# 1-4.net
KiCad netlist of a schematic drawn in EAGLE
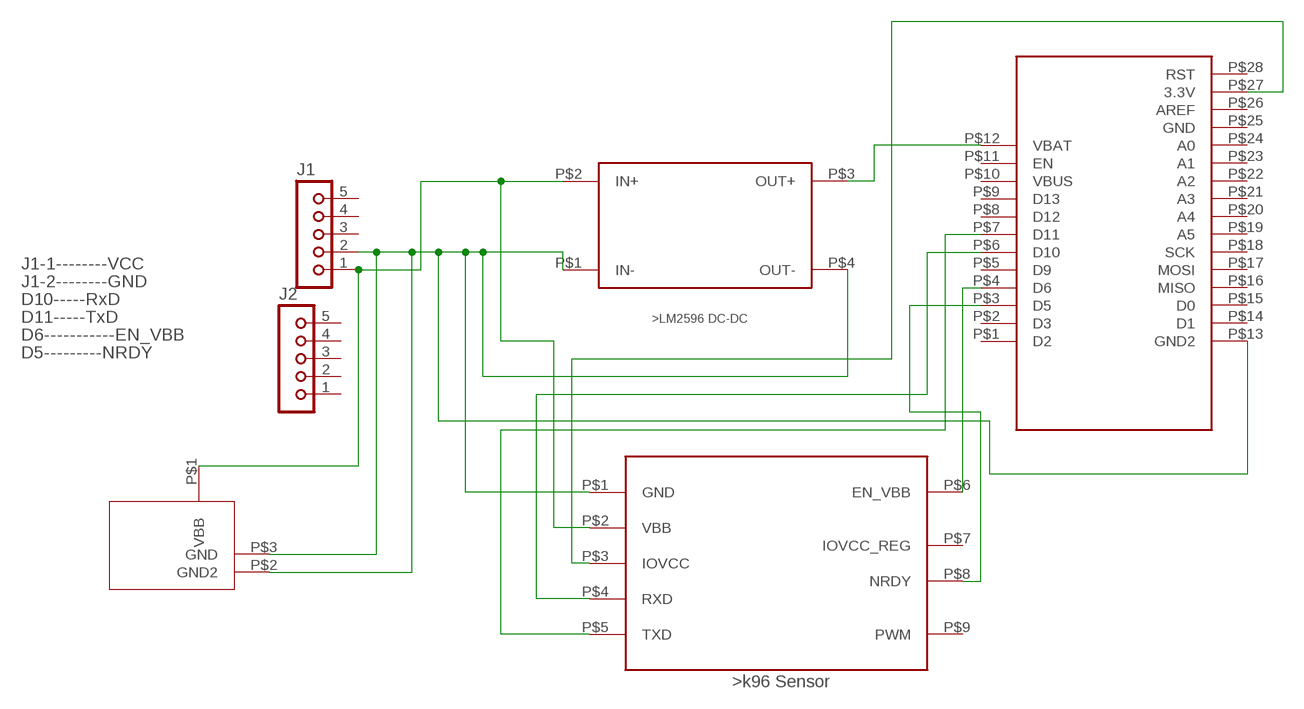
[diagram p0: schematic, sheet 1]

(export (version "E")
  (design (tool "Eeschema 10.0.6"))
  (components
    (comp (ref "DCDC1")
      (value "DCDC")
      (footprint "eagle-import:DCDC")
      (libsource (lib "eagle-import") (part "DCDC"))
    )
    (comp (ref "FEATHER1")
      (value "FEATHER")
      (footprint "eagle-import:FEATHER")
      (libsource (lib "eagle-import") (part "FEATHER"))
    )
    (comp (ref "J1")
      (value "JU05")
      (footprint "eagle-import:JU05")
      (libsource (lib "eagle-import") (part "JU05"))
    )
    (comp (ref "J2")
      (value "JU05")
      (footprint "eagle-import:JU05")
      (libsource (lib "eagle-import") (part "JU05"))
    )
    (comp (ref "K96SENSOR1")
      (value "K96SENSOR")
      (footprint "eagle-import:K96SENSOR")
      (libsource (lib "eagle-import") (part "K96SENSOR"))
    )
    (comp (ref "U$1")
      (value "POWER")
      (footprint "eagle-import:POWERIN")
      (libsource (lib "eagle-import") (part "POWER"))
    )
  )
  (nets
    (net (code "1") (name "Net-(DCDC1-IN+)") (class "Default")
      (node (ref "DCDC1") (pin "P$2") (pinfunction "IN+_P$2") (pintype "bidirectional"))
      (node (ref "J1") (pin "1") (pinfunction "1_1") (pintype "passive"))
      (node (ref "K96SENSOR1") (pin "P$2") (pinfunction "VBB_P$2") (pintype "bidirectional"))
      (node (ref "U$1") (pin "P$1") (pinfunction "VBB_P$1") (pintype "bidirectional"))
    )
    (net (code "2") (name "Net-(DCDC1-IN-)") (class "Default")
      (node (ref "DCDC1") (pin "P$1") (pinfunction "IN-_P$1") (pintype "bidirectional"))
      (node (ref "DCDC1") (pin "P$4") (pinfunction "OUT-_P$4") (pintype "bidirectional"))
      (node (ref "FEATHER1") (pin "P$13") (pinfunction "GND2_P$13") (pintype "bidirectional"))
      (node (ref "J1") (pin "2") (pinfunction "2_2") (pintype "passive"))
      (node (ref "K96SENSOR1") (pin "P$1") (pinfunction "GND_P$1") (pintype "bidirectional"))
      (node (ref "U$1") (pin "P$2") (pinfunction "GND2_P$2") (pintype "bidirectional"))
      (node (ref "U$1") (pin "P$3") (pinfunction "GND_P$3") (pintype "bidirectional"))
    )
    (net (code "3") (name "Net-(DCDC1-OUT+)") (class "Default")
      (node (ref "DCDC1") (pin "P$3") (pinfunction "OUT+_P$3") (pintype "bidirectional"))
      (node (ref "FEATHER1") (pin "P$12") (pinfunction "VBAT_P$12") (pintype "bidirectional"))
    )
    (net (code "4") (name "Net-(FEATHER1-3.3V)") (class "Default")
      (node (ref "FEATHER1") (pin "P$27") (pinfunction "3.3V_P$27") (pintype "bidirectional"))
      (node (ref "K96SENSOR1") (pin "P$3") (pinfunction "IOVCC_P$3") (pintype "bidirectional"))
    )
    (net (code "5") (name "Net-(FEATHER1-D5)") (class "Default")
      (node (ref "FEATHER1") (pin "P$3") (pinfunction "D5_P$3") (pintype "bidirectional"))
      (node (ref "K96SENSOR1") (pin "P$8") (pinfunction "NRDY_P$8") (pintype "bidirectional"))
    )
    (net (code "6") (name "Net-(FEATHER1-D6)") (class "Default")
      (node (ref "FEATHER1") (pin "P$4") (pinfunction "D6_P$4") (pintype "bidirectional"))
      (node (ref "K96SENSOR1") (pin "P$6") (pinfunction "EN_VBB_P$6") (pintype "bidirectional"))
    )
    (net (code "7") (name "Net-(FEATHER1-D10)") (class "Default")
      (node (ref "FEATHER1") (pin "P$6") (pinfunction "D10_P$6") (pintype "bidirectional"))
      (node (ref "K96SENSOR1") (pin "P$4") (pinfunction "RXD_P$4") (pintype "bidirectional"))
    )
    (net (code "8") (name "Net-(FEATHER1-D11)") (class "Default")
      (node (ref "FEATHER1") (pin "P$7") (pinfunction "D11_P$7") (pintype "bidirectional"))
      (node (ref "K96SENSOR1") (pin "P$5") (pinfunction "TXD_P$5") (pintype "bidirectional"))
    )
    (net (code "9") (name "unconnected-(FEATHER1-A0-PadP$24)") (class "Default")
      (node (ref "FEATHER1") (pin "P$24") (pinfunction "A0_P$24") (pintype "bidirectional"))
    )
    (net (code "10") (name "unconnected-(FEATHER1-A1-PadP$23)") (class "Default")
      (node (ref "FEATHER1") (pin "P$23") (pinfunction "A1_P$23") (pintype "bidirectional"))
    )
    (net (code "11") (name "unconnected-(FEATHER1-A2-PadP$22)") (class "Default")
      (node (ref "FEATHER1") (pin "P$22") (pinfunction "A2_P$22") (pintype "bidirectional"))
    )
    (net (code "12") (name "unconnected-(FEATHER1-A3-PadP$21)") (class "Default")
      (node (ref "FEATHER1") (pin "P$21") (pinfunction "A3_P$21") (pintype "bidirectional"))
    )
    (net (code "13") (name "unconnected-(FEATHER1-A4-PadP$20)") (class "Default")
      (node (ref "FEATHER1") (pin "P$20") (pinfunction "A4_P$20") (pintype "bidirectional"))
    )
    (net (code "14") (name "unconnected-(FEATHER1-A5-PadP$19)") (class "Default")
      (node (ref "FEATHER1") (pin "P$19") (pinfunction "A5_P$19") (pintype "bidirectional"))
    )
    (net (code "15") (name "unconnected-(FEATHER1-AREF-PadP$26)") (class "Default")
      (node (ref "FEATHER1") (pin "P$26") (pinfunction "AREF_P$26") (pintype "bidirectional"))
    )
    (net (code "16") (name "unconnected-(FEATHER1-D0-PadP$15)") (class "Default")
      (node (ref "FEATHER1") (pin "P$15") (pinfunction "D0_P$15") (pintype "bidirectional"))
    )
    (net (code "17") (name "unconnected-(FEATHER1-D1-PadP$14)") (class "Default")
      (node (ref "FEATHER1") (pin "P$14") (pinfunction "D1_P$14") (pintype "bidirectional"))
    )
    (net (code "18") (name "unconnected-(FEATHER1-D2-PadP$1)") (class "Default")
      (node (ref "FEATHER1") (pin "P$1") (pinfunction "D2_P$1") (pintype "bidirectional"))
    )
    (net (code "19") (name "unconnected-(FEATHER1-D3-PadP$2)") (class "Default")
      (node (ref "FEATHER1") (pin "P$2") (pinfunction "D3_P$2") (pintype "bidirectional"))
    )
    (net (code "20") (name "unconnected-(FEATHER1-D9-PadP$5)") (class "Default")
      (node (ref "FEATHER1") (pin "P$5") (pinfunction "D9_P$5") (pintype "bidirectional"))
    )
    (net (code "21") (name "unconnected-(FEATHER1-D12-PadP$8)") (class "Default")
      (node (ref "FEATHER1") (pin "P$8") (pinfunction "D12_P$8") (pintype "bidirectional"))
    )
    (net (code "22") (name "unconnected-(FEATHER1-D13-PadP$9)") (class "Default")
      (node (ref "FEATHER1") (pin "P$9") (pinfunction "D13_P$9") (pintype "bidirectional"))
    )
    (net (code "23") (name "unconnected-(FEATHER1-EN-PadP$11)") (class "Default")
      (node (ref "FEATHER1") (pin "P$11") (pinfunction "EN_P$11") (pintype "bidirectional"))
    )
    (net (code "24") (name "unconnected-(FEATHER1-GND-PadP$25)") (class "Default")
      (node (ref "FEATHER1") (pin "P$25") (pinfunction "GND_P$25") (pintype "bidirectional"))
    )
    (net (code "25") (name "unconnected-(FEATHER1-MISO-PadP$16)") (class "Default")
      (node (ref "FEATHER1") (pin "P$16") (pinfunction "MISO_P$16") (pintype "bidirectional"))
    )
    (net (code "26") (name "unconnected-(FEATHER1-MOSI-PadP$17)") (class "Default")
      (node (ref "FEATHER1") (pin "P$17") (pinfunction "MOSI_P$17") (pintype "bidirectional"))
    )
    (net (code "27") (name "unconnected-(FEATHER1-RST-PadP$28)") (class "Default")
      (node (ref "FEATHER1") (pin "P$28") (pinfunction "RST_P$28") (pintype "bidirectional"))
    )
    (net (code "28") (name "unconnected-(FEATHER1-SCK-PadP$18)") (class "Default")
      (node (ref "FEATHER1") (pin "P$18") (pinfunction "SCK_P$18") (pintype "bidirectional"))
    )
    (net (code "29") (name "unconnected-(FEATHER1-VBUS-PadP$10)") (class "Default")
      (node (ref "FEATHER1") (pin "P$10") (pinfunction "VBUS_P$10") (pintype "bidirectional"))
    )
    (net (code "30") (name "unconnected-(J1-Pad3)") (class "Default")
      (node (ref "J1") (pin "3") (pinfunction "3_3") (pintype "passive"))
    )
    (net (code "31") (name "unconnected-(J1-Pad4)") (class "Default")
      (node (ref "J1") (pin "4") (pinfunction "4_4") (pintype "passive"))
    )
    (net (code "32") (name "unconnected-(J1-Pad5)") (class "Default")
      (node (ref "J1") (pin "5") (pinfunction "5_5") (pintype "passive"))
    )
    (net (code "33") (name "unconnected-(J2-Pad1)") (class "Default")
      (node (ref "J2") (pin "1") (pinfunction "1_1") (pintype "passive"))
    )
    (net (code "34") (name "unconnected-(J2-Pad2)") (class "Default")
      (node (ref "J2") (pin "2") (pinfunction "2_2") (pintype "passive"))
    )
    (net (code "35") (name "unconnected-(J2-Pad3)") (class "Default")
      (node (ref "J2") (pin "3") (pinfunction "3_3") (pintype "passive"))
    )
    (net (code "36") (name "unconnected-(J2-Pad4)") (class "Default")
      (node (ref "J2") (pin "4") (pinfunction "4_4") (pintype "passive"))
    )
    (net (code "37") (name "unconnected-(J2-Pad5)") (class "Default")
      (node (ref "J2") (pin "5") (pinfunction "5_5") (pintype "passive"))
    )
    (net (code "38") (name "unconnected-(K96SENSOR1-IOVCC_REG-PadP$7)") (class "Default")
      (node (ref "K96SENSOR1") (pin "P$7") (pinfunction "IOVCC_REG_P$7") (pintype "bidirectional"))
    )
    (net (code "39") (name "unconnected-(K96SENSOR1-PWM-PadP$9)") (class "Default")
      (node (ref "K96SENSOR1") (pin "P$9") (pinfunction "PWM_P$9") (pintype "bidirectional"))
    )
  )
)
